# p2hex-001.net
KiCad netlist of a schematic drawn in EAGLE
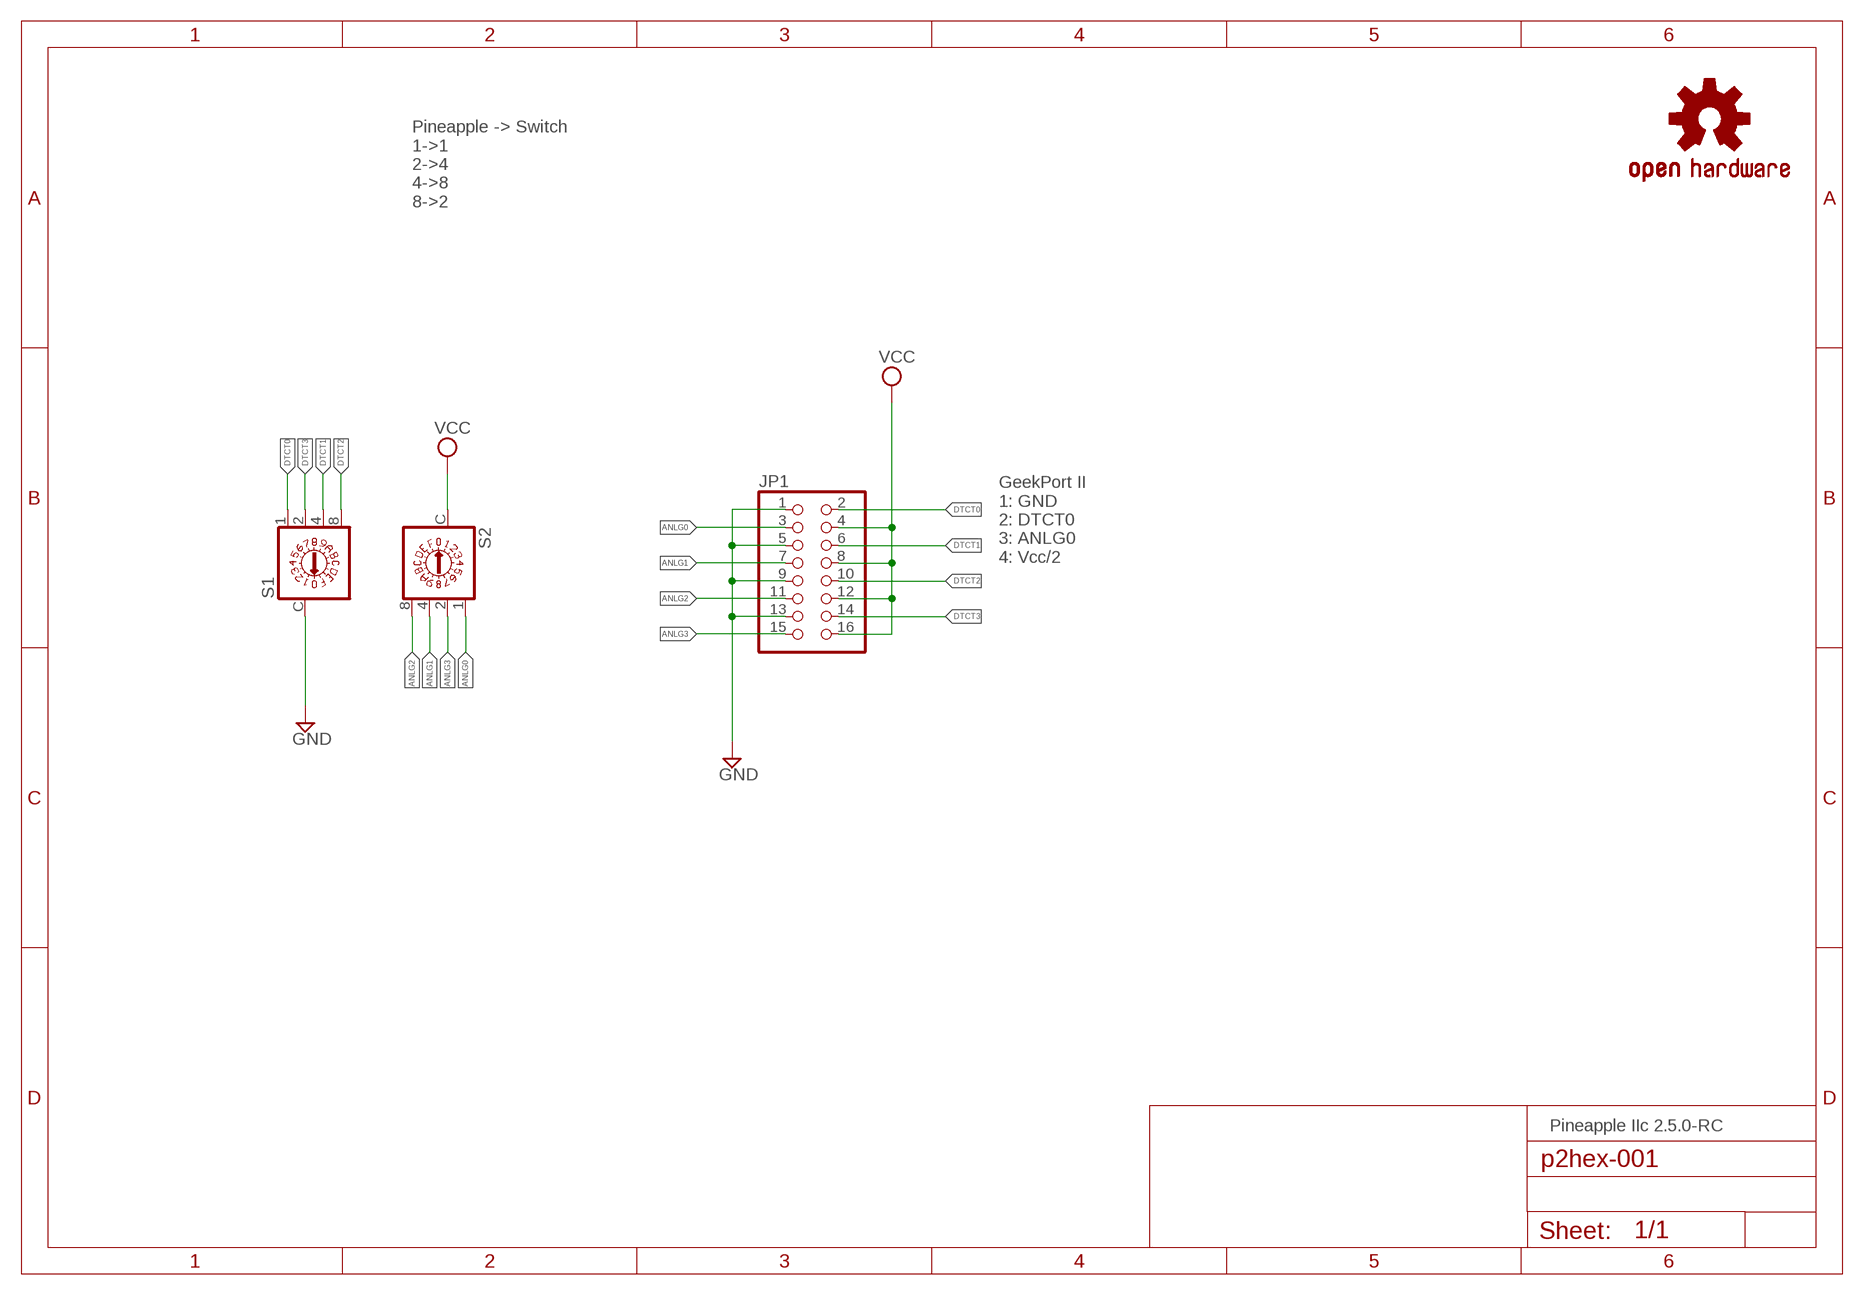
[diagram p0: schematic, sheet 1]

(export (version "E")
  (design (tool "Eeschema 10.0.6"))
  (components
    (comp (ref "JP1")
      (value "PINHD-2X8")
      (footprint "eagle-import:2X08")
      (libsource (lib "eagle-import") (part "PINHD-2X8"))
    )
    (comp (ref "LOGO1")
      (value "OSHW-LOGOS-COPPER")
      (footprint "eagle-import:OSHW-LOGO-S_COPPER")
      (libsource (lib "eagle-import") (part "OSHW-LOGOS-COPPER"))
    )
    (comp (ref "S1")
      (value "A1353HEX")
      (footprint "eagle-import:A1353HEX")
      (libsource (lib "eagle-import") (part "A1353HEX"))
    )
    (comp (ref "S2")
      (value "A1353HEX")
      (footprint "eagle-import:A1353HEX")
      (libsource (lib "eagle-import") (part "A1353HEX"))
    )
  )
  (nets
    (net (code "1") (name "ANLG0") (class "Default")
      (node (ref "JP1") (pin "3") (pinfunction "3_3") (pintype "passive"))
      (node (ref "S2") (pin "1") (pinfunction "1_1") (pintype "passive"))
    )
    (net (code "2") (name "ANLG1") (class "Default")
      (node (ref "JP1") (pin "7") (pinfunction "7_7") (pintype "passive"))
      (node (ref "S2") (pin "4") (pinfunction "4_4") (pintype "passive"))
    )
    (net (code "3") (name "ANLG2") (class "Default")
      (node (ref "JP1") (pin "11") (pinfunction "11_11") (pintype "passive"))
      (node (ref "S2") (pin "8") (pinfunction "8_8") (pintype "passive"))
    )
    (net (code "4") (name "ANLG3") (class "Default")
      (node (ref "JP1") (pin "15") (pinfunction "15_15") (pintype "passive"))
      (node (ref "S2") (pin "2") (pinfunction "2_2") (pintype "passive"))
    )
    (net (code "5") (name "DTCT0") (class "Default")
      (node (ref "JP1") (pin "2") (pinfunction "2_2") (pintype "passive"))
      (node (ref "S1") (pin "1") (pinfunction "1_1") (pintype "passive"))
    )
    (net (code "6") (name "DTCT1") (class "Default")
      (node (ref "JP1") (pin "6") (pinfunction "6_6") (pintype "passive"))
      (node (ref "S1") (pin "4") (pinfunction "4_4") (pintype "passive"))
    )
    (net (code "7") (name "DTCT2") (class "Default")
      (node (ref "JP1") (pin "10") (pinfunction "10_10") (pintype "passive"))
      (node (ref "S1") (pin "8") (pinfunction "8_8") (pintype "passive"))
    )
    (net (code "8") (name "DTCT3") (class "Default")
      (node (ref "JP1") (pin "14") (pinfunction "14_14") (pintype "passive"))
      (node (ref "S1") (pin "2") (pinfunction "2_2") (pintype "passive"))
    )
    (net (code "9") (name "GND") (class "Default")
      (node (ref "JP1") (pin "1") (pinfunction "1_1") (pintype "passive"))
      (node (ref "JP1") (pin "13") (pinfunction "13_13") (pintype "passive"))
      (node (ref "JP1") (pin "5") (pinfunction "5_5") (pintype "passive"))
      (node (ref "JP1") (pin "9") (pinfunction "9_9") (pintype "passive"))
      (node (ref "S1") (pin "C") (pinfunction "C_C") (pintype "passive"))
    )
    (net (code "10") (name "VCC") (class "Default")
      (node (ref "JP1") (pin "12") (pinfunction "12_12") (pintype "passive"))
      (node (ref "JP1") (pin "16") (pinfunction "16_16") (pintype "passive"))
      (node (ref "JP1") (pin "4") (pinfunction "4_4") (pintype "passive"))
      (node (ref "JP1") (pin "8") (pinfunction "8_8") (pintype "passive"))
      (node (ref "S2") (pin "C") (pinfunction "C_C") (pintype "passive"))
    )
  )
)
